# JMP_2_0.net
KiCad netlist of a schematic drawn in EAGLE
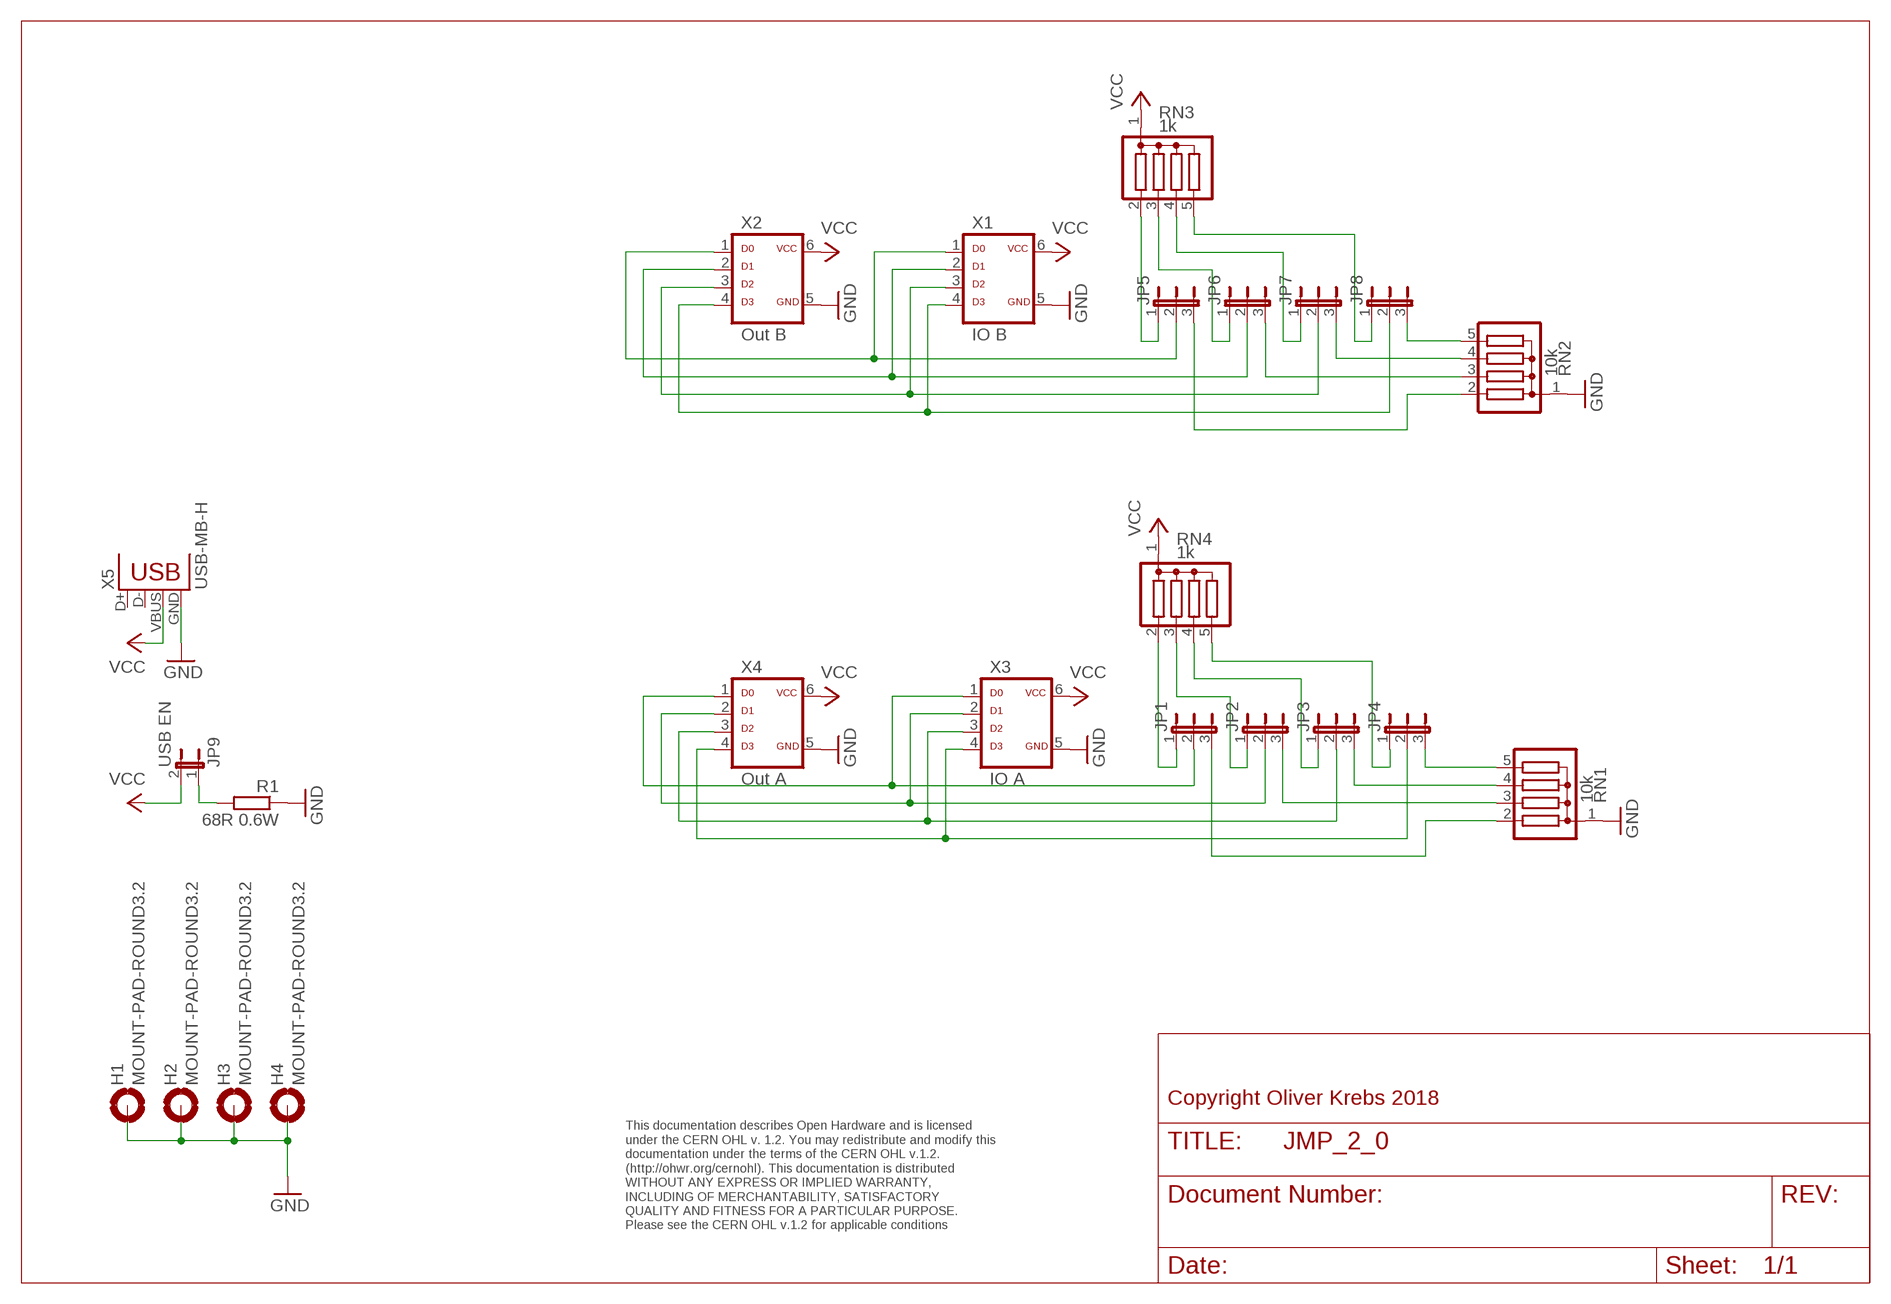
[diagram p0: schematic, sheet 1]

(export (version "E")
  (design (tool "Eeschema 10.0.6"))
  (components
    (comp (ref "H1")
      (value "MOUNT-PAD-ROUND3.2")
      (footprint "eagle-import:3,2-PAD")
      (libsource (lib "eagle-import") (part "MOUNT-PAD-ROUND3.2"))
    )
    (comp (ref "H2")
      (value "MOUNT-PAD-ROUND3.2")
      (footprint "eagle-import:3,2-PAD")
      (libsource (lib "eagle-import") (part "MOUNT-PAD-ROUND3.2"))
    )
    (comp (ref "H3")
      (value "MOUNT-PAD-ROUND3.2")
      (footprint "eagle-import:3,2-PAD")
      (libsource (lib "eagle-import") (part "MOUNT-PAD-ROUND3.2"))
    )
    (comp (ref "H4")
      (value "MOUNT-PAD-ROUND3.2")
      (footprint "eagle-import:3,2-PAD")
      (libsource (lib "eagle-import") (part "MOUNT-PAD-ROUND3.2"))
    )
    (comp (ref "JP1")
      (value "JP2E")
      (footprint "eagle-import:JP2-S")
      (libsource (lib "eagle-import") (part "JP2E"))
    )
    (comp (ref "JP2")
      (value "JP2E")
      (footprint "eagle-import:JP2-S")
      (libsource (lib "eagle-import") (part "JP2E"))
    )
    (comp (ref "JP3")
      (value "JP2E")
      (footprint "eagle-import:JP2-S")
      (libsource (lib "eagle-import") (part "JP2E"))
    )
    (comp (ref "JP4")
      (value "JP2E")
      (footprint "eagle-import:JP2-S")
      (libsource (lib "eagle-import") (part "JP2E"))
    )
    (comp (ref "JP5")
      (value "JP2E")
      (footprint "eagle-import:JP2-S")
      (libsource (lib "eagle-import") (part "JP2E"))
    )
    (comp (ref "JP6")
      (value "JP2E")
      (footprint "eagle-import:JP2-S")
      (libsource (lib "eagle-import") (part "JP2E"))
    )
    (comp (ref "JP7")
      (value "JP2E")
      (footprint "eagle-import:JP2-S")
      (libsource (lib "eagle-import") (part "JP2E"))
    )
    (comp (ref "JP8")
      (value "JP2E")
      (footprint "eagle-import:JP2-S")
      (libsource (lib "eagle-import") (part "JP2E"))
    )
    (comp (ref "JP9")
      (value "USB EN")
      (footprint "eagle-import:JP1")
      (libsource (lib "eagle-import") (part "JP1E"))
    )
    (comp (ref "R1")
      (value "68R 0.6W")
      (footprint "eagle-import:0207_10")
      (libsource (lib "eagle-import") (part "R-EU_0207/10"))
    )
    (comp (ref "RN1")
      (value "10k")
      (footprint "eagle-import:SIL5")
      (libsource (lib "eagle-import") (part "G04R"))
    )
    (comp (ref "RN2")
      (value "10k")
      (footprint "eagle-import:SIL5")
      (libsource (lib "eagle-import") (part "G04R"))
    )
    (comp (ref "RN3")
      (value "1k")
      (footprint "eagle-import:SIL5")
      (libsource (lib "eagle-import") (part "G04R"))
    )
    (comp (ref "RN4")
      (value "1k")
      (footprint "eagle-import:SIL5")
      (libsource (lib "eagle-import") (part "G04R"))
    )
    (comp (ref "X1")
      (value "IO B")
      (footprint "eagle-import:ML-6")
      (libsource (lib "eagle-import") (part "ML6D"))
    )
    (comp (ref "X2")
      (value "Out B")
      (footprint "eagle-import:ML-6")
      (libsource (lib "eagle-import") (part "ML6D"))
    )
    (comp (ref "X3")
      (value "IO A")
      (footprint "eagle-import:ML-6")
      (libsource (lib "eagle-import") (part "ML6D"))
    )
    (comp (ref "X4")
      (value "Out A")
      (footprint "eagle-import:ML-6")
      (libsource (lib "eagle-import") (part "ML6D"))
    )
    (comp (ref "X5")
      (value "USB-MB-H")
      (footprint "eagle-import:USB-MB-H")
      (libsource (lib "eagle-import") (part "USB-MB-H"))
    )
  )
  (nets
    (net (code "1") (name "GND") (class "Default")
      (node (ref "H1") (pin "B3,2") (pinfunction "MOUNT_B3,2") (pintype "passive"))
      (node (ref "H2") (pin "B3,2") (pinfunction "MOUNT_B3,2") (pintype "passive"))
      (node (ref "H3") (pin "B3,2") (pinfunction "MOUNT_B3,2") (pintype "passive"))
      (node (ref "H4") (pin "B3,2") (pinfunction "MOUNT_B3,2") (pintype "passive"))
      (node (ref "R1") (pin "1") (pinfunction "1_1") (pintype "passive"))
      (node (ref "RN1") (pin "1") (pinfunction "1_1") (pintype "passive"))
      (node (ref "RN2") (pin "1") (pinfunction "1_1") (pintype "passive"))
      (node (ref "X1") (pin "5") (pinfunction "5_5") (pintype "passive"))
      (node (ref "X2") (pin "5") (pinfunction "5_5") (pintype "passive"))
      (node (ref "X3") (pin "5") (pinfunction "5_5") (pintype "passive"))
      (node (ref "X4") (pin "5") (pinfunction "5_5") (pintype "passive"))
      (node (ref "X5") (pin "GND") (pinfunction "GND_GND") (pintype "bidirectional"))
    )
    (net (code "2") (name "Net-(JP1-Pad1)") (class "Default")
      (node (ref "JP1") (pin "1") (pinfunction "1_1") (pintype "passive"))
      (node (ref "RN4") (pin "2") (pinfunction "2_2") (pintype "passive"))
    )
    (net (code "3") (name "Net-(JP1-Pad2)") (class "Default")
      (node (ref "JP1") (pin "2") (pinfunction "2_2") (pintype "passive"))
      (node (ref "X3") (pin "1") (pinfunction "1_1") (pintype "passive"))
      (node (ref "X4") (pin "1") (pinfunction "1_1") (pintype "passive"))
    )
    (net (code "4") (name "Net-(JP1-Pad3)") (class "Default")
      (node (ref "JP1") (pin "3") (pinfunction "3_3") (pintype "passive"))
      (node (ref "RN1") (pin "2") (pinfunction "2_2") (pintype "passive"))
    )
    (net (code "5") (name "Net-(JP2-Pad1)") (class "Default")
      (node (ref "JP2") (pin "1") (pinfunction "1_1") (pintype "passive"))
      (node (ref "RN4") (pin "3") (pinfunction "3_3") (pintype "passive"))
    )
    (net (code "6") (name "Net-(JP2-Pad2)") (class "Default")
      (node (ref "JP2") (pin "2") (pinfunction "2_2") (pintype "passive"))
      (node (ref "X3") (pin "2") (pinfunction "2_2") (pintype "passive"))
      (node (ref "X4") (pin "2") (pinfunction "2_2") (pintype "passive"))
    )
    (net (code "7") (name "Net-(JP2-Pad3)") (class "Default")
      (node (ref "JP2") (pin "3") (pinfunction "3_3") (pintype "passive"))
      (node (ref "RN1") (pin "3") (pinfunction "3_3") (pintype "passive"))
    )
    (net (code "8") (name "Net-(JP3-Pad1)") (class "Default")
      (node (ref "JP3") (pin "1") (pinfunction "1_1") (pintype "passive"))
      (node (ref "RN4") (pin "4") (pinfunction "4_4") (pintype "passive"))
    )
    (net (code "9") (name "Net-(JP3-Pad2)") (class "Default")
      (node (ref "JP3") (pin "2") (pinfunction "2_2") (pintype "passive"))
      (node (ref "X3") (pin "3") (pinfunction "3_3") (pintype "passive"))
      (node (ref "X4") (pin "3") (pinfunction "3_3") (pintype "passive"))
    )
    (net (code "10") (name "Net-(JP3-Pad3)") (class "Default")
      (node (ref "JP3") (pin "3") (pinfunction "3_3") (pintype "passive"))
      (node (ref "RN1") (pin "4") (pinfunction "4_4") (pintype "passive"))
    )
    (net (code "11") (name "Net-(JP4-Pad1)") (class "Default")
      (node (ref "JP4") (pin "1") (pinfunction "1_1") (pintype "passive"))
      (node (ref "RN4") (pin "5") (pinfunction "5_5") (pintype "passive"))
    )
    (net (code "12") (name "Net-(JP4-Pad2)") (class "Default")
      (node (ref "JP4") (pin "2") (pinfunction "2_2") (pintype "passive"))
      (node (ref "X3") (pin "4") (pinfunction "4_4") (pintype "passive"))
      (node (ref "X4") (pin "4") (pinfunction "4_4") (pintype "passive"))
    )
    (net (code "13") (name "Net-(JP4-Pad3)") (class "Default")
      (node (ref "JP4") (pin "3") (pinfunction "3_3") (pintype "passive"))
      (node (ref "RN1") (pin "5") (pinfunction "5_5") (pintype "passive"))
    )
    (net (code "14") (name "Net-(JP5-Pad1)") (class "Default")
      (node (ref "JP5") (pin "1") (pinfunction "1_1") (pintype "passive"))
      (node (ref "RN3") (pin "2") (pinfunction "2_2") (pintype "passive"))
    )
    (net (code "15") (name "Net-(JP5-Pad2)") (class "Default")
      (node (ref "JP5") (pin "2") (pinfunction "2_2") (pintype "passive"))
      (node (ref "X1") (pin "1") (pinfunction "1_1") (pintype "passive"))
      (node (ref "X2") (pin "1") (pinfunction "1_1") (pintype "passive"))
    )
    (net (code "16") (name "Net-(JP5-Pad3)") (class "Default")
      (node (ref "JP5") (pin "3") (pinfunction "3_3") (pintype "passive"))
      (node (ref "RN2") (pin "2") (pinfunction "2_2") (pintype "passive"))
    )
    (net (code "17") (name "Net-(JP6-Pad1)") (class "Default")
      (node (ref "JP6") (pin "1") (pinfunction "1_1") (pintype "passive"))
      (node (ref "RN3") (pin "3") (pinfunction "3_3") (pintype "passive"))
    )
    (net (code "18") (name "Net-(JP6-Pad2)") (class "Default")
      (node (ref "JP6") (pin "2") (pinfunction "2_2") (pintype "passive"))
      (node (ref "X1") (pin "2") (pinfunction "2_2") (pintype "passive"))
      (node (ref "X2") (pin "2") (pinfunction "2_2") (pintype "passive"))
    )
    (net (code "19") (name "Net-(JP6-Pad3)") (class "Default")
      (node (ref "JP6") (pin "3") (pinfunction "3_3") (pintype "passive"))
      (node (ref "RN2") (pin "3") (pinfunction "3_3") (pintype "passive"))
    )
    (net (code "20") (name "Net-(JP7-Pad1)") (class "Default")
      (node (ref "JP7") (pin "1") (pinfunction "1_1") (pintype "passive"))
      (node (ref "RN3") (pin "4") (pinfunction "4_4") (pintype "passive"))
    )
    (net (code "21") (name "Net-(JP7-Pad2)") (class "Default")
      (node (ref "JP7") (pin "2") (pinfunction "2_2") (pintype "passive"))
      (node (ref "X1") (pin "3") (pinfunction "3_3") (pintype "passive"))
      (node (ref "X2") (pin "3") (pinfunction "3_3") (pintype "passive"))
    )
    (net (code "22") (name "Net-(JP7-Pad3)") (class "Default")
      (node (ref "JP7") (pin "3") (pinfunction "3_3") (pintype "passive"))
      (node (ref "RN2") (pin "4") (pinfunction "4_4") (pintype "passive"))
    )
    (net (code "23") (name "Net-(JP8-Pad1)") (class "Default")
      (node (ref "JP8") (pin "1") (pinfunction "1_1") (pintype "passive"))
      (node (ref "RN3") (pin "5") (pinfunction "5_5") (pintype "passive"))
    )
    (net (code "24") (name "Net-(JP8-Pad2)") (class "Default")
      (node (ref "JP8") (pin "2") (pinfunction "2_2") (pintype "passive"))
      (node (ref "X1") (pin "4") (pinfunction "4_4") (pintype "passive"))
      (node (ref "X2") (pin "4") (pinfunction "4_4") (pintype "passive"))
    )
    (net (code "25") (name "Net-(JP8-Pad3)") (class "Default")
      (node (ref "JP8") (pin "3") (pinfunction "3_3") (pintype "passive"))
      (node (ref "RN2") (pin "5") (pinfunction "5_5") (pintype "passive"))
    )
    (net (code "26") (name "Net-(JP9-Pad1)") (class "Default")
      (node (ref "JP9") (pin "1") (pinfunction "1_1") (pintype "passive"))
      (node (ref "R1") (pin "2") (pinfunction "2_2") (pintype "passive"))
    )
    (net (code "27") (name "VCC") (class "Default")
      (node (ref "JP9") (pin "2") (pinfunction "2_2") (pintype "passive"))
      (node (ref "RN3") (pin "1") (pinfunction "1_1") (pintype "passive"))
      (node (ref "RN4") (pin "1") (pinfunction "1_1") (pintype "passive"))
      (node (ref "X1") (pin "6") (pinfunction "6_6") (pintype "passive"))
      (node (ref "X2") (pin "6") (pinfunction "6_6") (pintype "passive"))
      (node (ref "X3") (pin "6") (pinfunction "6_6") (pintype "passive"))
      (node (ref "X4") (pin "6") (pinfunction "6_6") (pintype "passive"))
      (node (ref "X5") (pin "VBUS") (pinfunction "VBUS_VBUS") (pintype "bidirectional"))
    )
    (net (code "28") (name "unconnected-(X5-PadD+)") (class "Default")
      (node (ref "X5") (pin "D+") (pinfunction "D+_D+") (pintype "bidirectional"))
    )
    (net (code "29") (name "unconnected-(X5-PadD-)") (class "Default")
      (node (ref "X5") (pin "D-") (pinfunction "D-_D-") (pintype "bidirectional"))
    )
  )
)
